# ludusProtoShieldWireless.net
KiCad netlist of a schematic drawn in EAGLE
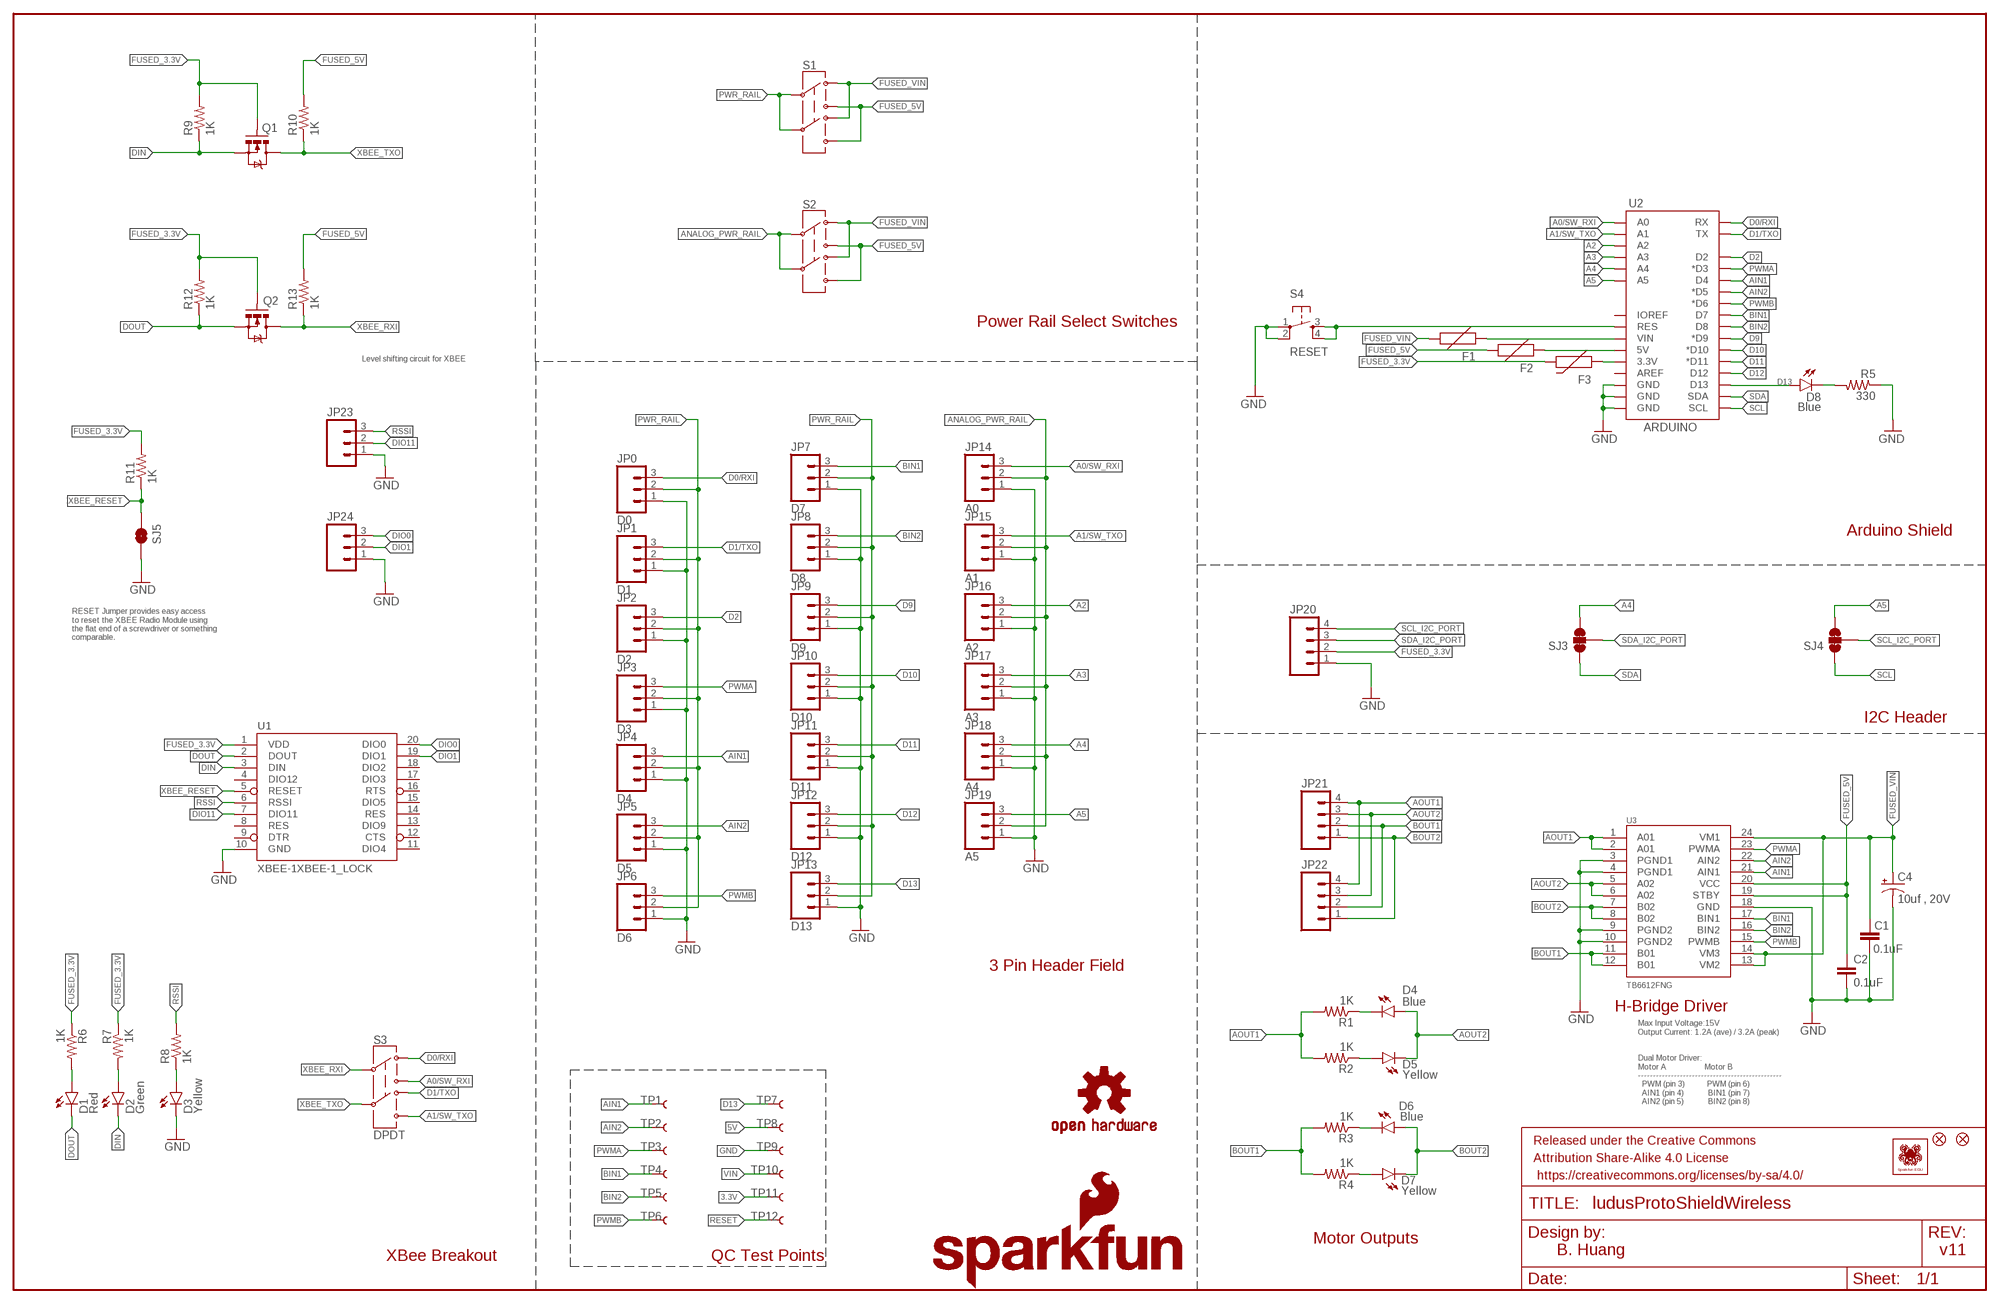
[diagram p0: schematic, sheet 1]

(export (version "E")
  (design (tool "Eeschema 10.0.6"))
  (components
    (comp (ref "C1")
      (value "0.1uF")
      (footprint "eagle-import:0603-CAP")
      (libsource (lib "eagle-import") (part "0.1UF-25V-5%(0603)"))
    )
    (comp (ref "C2")
      (value "0.1uF")
      (footprint "eagle-import:0603-CAP")
      (libsource (lib "eagle-import") (part "0.1UF-25V-5%(0603)"))
    )
    (comp (ref "C4")
      (value "10uf , 20V")
      (footprint "eagle-import:EIA3528")
      (libsource (lib "eagle-import") (part "10UF-20V-10%(TANT)"))
    )
    (comp (ref "D1")
      (value "Red")
      (footprint "eagle-import:LED-0603")
      (libsource (lib "eagle-import") (part "LED-RED0603"))
    )
    (comp (ref "D2")
      (value "Green")
      (footprint "eagle-import:LED-0603")
      (libsource (lib "eagle-import") (part "LED-GREEN0603"))
    )
    (comp (ref "D3")
      (value "Yellow")
      (footprint "eagle-import:LED-0603")
      (libsource (lib "eagle-import") (part "LED-YELLOW0603"))
    )
    (comp (ref "D4")
      (value "Blue")
      (footprint "eagle-import:LED-0603")
      (libsource (lib "eagle-import") (part "LED-BLUE0603"))
    )
    (comp (ref "D5")
      (value "Yellow")
      (footprint "eagle-import:LED-0603")
      (libsource (lib "eagle-import") (part "LED-YELLOW0603"))
    )
    (comp (ref "D6")
      (value "Blue")
      (footprint "eagle-import:LED-0603")
      (libsource (lib "eagle-import") (part "LED-BLUE0603"))
    )
    (comp (ref "D7")
      (value "Yellow")
      (footprint "eagle-import:LED-0603")
      (libsource (lib "eagle-import") (part "LED-YELLOW0603"))
    )
    (comp (ref "D8")
      (value "Blue")
      (footprint "eagle-import:LED-0603")
      (libsource (lib "eagle-import") (part "LED-BLUE0603"))
    )
    (comp (ref "F1")
      (value "PTCSMD")
      (footprint "eagle-import:PTC-1206")
      (libsource (lib "eagle-import") (part "PTCSMD"))
    )
    (comp (ref "F2")
      (value "PTCSMD")
      (footprint "eagle-import:PTC-1206")
      (libsource (lib "eagle-import") (part "PTCSMD"))
    )
    (comp (ref "F3")
      (value "PTCSMD")
      (footprint "eagle-import:PTC-1206")
      (libsource (lib "eagle-import") (part "PTCSMD"))
    )
    (comp (ref "FID1")
      (value "FIDUCIAL1X2")
      (footprint "eagle-import:FIDUCIAL-1X2")
      (libsource (lib "eagle-import") (part "FIDUCIAL1X2"))
    )
    (comp (ref "FID2")
      (value "FIDUCIAL1X2")
      (footprint "eagle-import:FIDUCIAL-1X2")
      (libsource (lib "eagle-import") (part "FIDUCIAL1X2"))
    )
    (comp (ref "FRAME1")
      (value "FRAME-LEDGER")
      (footprint "eagle-import:CREATIVE_COMMONS")
      (libsource (lib "eagle-import") (part "FRAME-LEDGER"))
    )
    (comp (ref "JP0")
      (value "D0")
      (footprint "eagle-import:1X03_LOCK")
      (libsource (lib "eagle-import") (part "M03LOCK"))
    )
    (comp (ref "JP1")
      (value "D1")
      (footprint "eagle-import:1X03_LOCK")
      (libsource (lib "eagle-import") (part "M03LOCK"))
    )
    (comp (ref "JP2")
      (value "D2")
      (footprint "eagle-import:1X03_LOCK")
      (libsource (lib "eagle-import") (part "M03LOCK"))
    )
    (comp (ref "JP3")
      (value "D3")
      (footprint "eagle-import:1X03_LOCK")
      (libsource (lib "eagle-import") (part "M03LOCK"))
    )
    (comp (ref "JP4")
      (value "D4")
      (footprint "eagle-import:1X03_LOCK")
      (libsource (lib "eagle-import") (part "M03LOCK"))
    )
    (comp (ref "JP5")
      (value "D5")
      (footprint "eagle-import:1X03_LOCK")
      (libsource (lib "eagle-import") (part "M03LOCK"))
    )
    (comp (ref "JP6")
      (value "D6")
      (footprint "eagle-import:1X03_LOCK")
      (libsource (lib "eagle-import") (part "M03LOCK"))
    )
    (comp (ref "JP7")
      (value "D7")
      (footprint "eagle-import:1X03_LOCK")
      (libsource (lib "eagle-import") (part "M03LOCK"))
    )
    (comp (ref "JP8")
      (value "D8")
      (footprint "eagle-import:1X03_LOCK")
      (libsource (lib "eagle-import") (part "M03LOCK"))
    )
    (comp (ref "JP9")
      (value "D9")
      (footprint "eagle-import:1X03_LOCK")
      (libsource (lib "eagle-import") (part "M03LOCK"))
    )
    (comp (ref "JP10")
      (value "D10")
      (footprint "eagle-import:1X03_LOCK")
      (libsource (lib "eagle-import") (part "M03LOCK"))
    )
    (comp (ref "JP11")
      (value "D11")
      (footprint "eagle-import:1X03_LOCK")
      (libsource (lib "eagle-import") (part "M03LOCK"))
    )
    (comp (ref "JP12")
      (value "D12")
      (footprint "eagle-import:1X03_LOCK")
      (libsource (lib "eagle-import") (part "M03LOCK"))
    )
    (comp (ref "JP13")
      (value "D13")
      (footprint "eagle-import:1X03_LOCK")
      (libsource (lib "eagle-import") (part "M03LOCK"))
    )
    (comp (ref "JP14")
      (value "A0")
      (footprint "eagle-import:1X03_LOCK")
      (libsource (lib "eagle-import") (part "M03LOCK"))
    )
    (comp (ref "JP15")
      (value "A1")
      (footprint "eagle-import:1X03_LOCK")
      (libsource (lib "eagle-import") (part "M03LOCK"))
    )
    (comp (ref "JP16")
      (value "A2")
      (footprint "eagle-import:1X03_LOCK")
      (libsource (lib "eagle-import") (part "M03LOCK"))
    )
    (comp (ref "JP17")
      (value "A3")
      (footprint "eagle-import:1X03_LOCK")
      (libsource (lib "eagle-import") (part "M03LOCK"))
    )
    (comp (ref "JP18")
      (value "A4")
      (footprint "eagle-import:1X03_LOCK")
      (libsource (lib "eagle-import") (part "M03LOCK"))
    )
    (comp (ref "JP19")
      (value "A5")
      (footprint "eagle-import:1X03_LOCK")
      (libsource (lib "eagle-import") (part "M03LOCK"))
    )
    (comp (ref "JP20")
      (value "M04PTH")
      (footprint "eagle-import:1X04")
      (libsource (lib "eagle-import") (part "M04PTH"))
    )
    (comp (ref "JP21")
      (value "M04PTH")
      (footprint "eagle-import:1X04")
      (libsource (lib "eagle-import") (part "M04PTH"))
    )
    (comp (ref "JP22")
      (value "M04LOCK")
      (footprint "eagle-import:1X04_LOCK")
      (libsource (lib "eagle-import") (part "M04LOCK"))
    )
    (comp (ref "JP23")
      (value "M031X03_NO_SILK")
      (footprint "eagle-import:1X03_NO_SILK")
      (libsource (lib "eagle-import") (part "M031X03_NO_SILK"))
    )
    (comp (ref "JP24")
      (value "M031X03_NO_SILK")
      (footprint "eagle-import:1X03_NO_SILK")
      (libsource (lib "eagle-import") (part "M031X03_NO_SILK"))
    )
    (comp (ref "LOGO1")
      (value "OSHW-LOGOM")
      (footprint "eagle-import:OSHW-LOGO-M")
      (libsource (lib "eagle-import") (part "OSHW-LOGOM"))
    )
    (comp (ref "LOGO2")
      (value "SFE_LOGO_NAME_FLAME.1_INCH")
      (footprint "eagle-import:SFE_LOGO_NAME_FLAME_.1")
      (libsource (lib "eagle-import") (part "SFE_LOGO_NAME_FLAME.1_INCH"))
    )
    (comp (ref "LOGO3")
      (value "SFE_LOGO_FLAME.2_INCH")
      (footprint "eagle-import:SFE_LOGO_FLAME_.2")
      (libsource (lib "eagle-import") (part "SFE_LOGO_FLAME.2_INCH"))
    )
    (comp (ref "LOGO4")
      (value "SFE_LOGO_NAME_FLAME.1_INCH")
      (footprint "eagle-import:SFE_LOGO_NAME_FLAME_.1")
      (libsource (lib "eagle-import") (part "SFE_LOGO_NAME_FLAME.1_INCH"))
    )
    (comp (ref "LOGO5")
      (value "SFE_LOGO_FLAME.2COP")
      (footprint "eagle-import:SFE_LOGO_FLAME_COPPER_.2")
      (libsource (lib "eagle-import") (part "SFE_LOGO_FLAME.2COP"))
    )
    (comp (ref "Q1")
      (value "MOSFET-NCHANNELBSS138")
      (footprint "eagle-import:SOT23-3")
      (libsource (lib "eagle-import") (part "MOSFET-NCHANNELBSS138"))
    )
    (comp (ref "Q2")
      (value "MOSFET-NCHANNELBSS138")
      (footprint "eagle-import:SOT23-3")
      (libsource (lib "eagle-import") (part "MOSFET-NCHANNELBSS138"))
    )
    (comp (ref "R1")
      (value "1K")
      (footprint "eagle-import:0603-RES")
      (libsource (lib "eagle-import") (part "1KOHM-1/10W-1%(0603)"))
    )
    (comp (ref "R2")
      (value "1K")
      (footprint "eagle-import:0603-RES")
      (libsource (lib "eagle-import") (part "1KOHM-1/10W-1%(0603)"))
    )
    (comp (ref "R3")
      (value "1K")
      (footprint "eagle-import:0603-RES")
      (libsource (lib "eagle-import") (part "1KOHM-1/10W-1%(0603)"))
    )
    (comp (ref "R4")
      (value "1K")
      (footprint "eagle-import:0603-RES")
      (libsource (lib "eagle-import") (part "1KOHM-1/10W-1%(0603)"))
    )
    (comp (ref "R5")
      (value "330")
      (footprint "eagle-import:0603-RES")
      (libsource (lib "eagle-import") (part "330OHM1/10W1%(0603)"))
    )
    (comp (ref "R6")
      (value "1K")
      (footprint "eagle-import:0603-RES")
      (libsource (lib "eagle-import") (part "1KOHM-1/10W-1%(0603)"))
    )
    (comp (ref "R7")
      (value "1K")
      (footprint "eagle-import:0603-RES")
      (libsource (lib "eagle-import") (part "1KOHM-1/10W-1%(0603)"))
    )
    (comp (ref "R8")
      (value "1K")
      (footprint "eagle-import:0603-RES")
      (libsource (lib "eagle-import") (part "1KOHM-1/10W-1%(0603)"))
    )
    (comp (ref "R9")
      (value "1K")
      (footprint "eagle-import:0603-RES")
      (libsource (lib "eagle-import") (part "1KOHM-1/10W-1%(0603)"))
    )
    (comp (ref "R10")
      (value "1K")
      (footprint "eagle-import:0603-RES")
      (libsource (lib "eagle-import") (part "1KOHM-1/10W-1%(0603)"))
    )
    (comp (ref "R11")
      (value "1K")
      (footprint "eagle-import:0603-RES")
      (libsource (lib "eagle-import") (part "1KOHM-1/10W-1%(0603)"))
    )
    (comp (ref "R12")
      (value "1K")
      (footprint "eagle-import:0603-RES")
      (libsource (lib "eagle-import") (part "1KOHM-1/10W-1%(0603)"))
    )
    (comp (ref "R13")
      (value "1K")
      (footprint "eagle-import:0603-RES")
      (libsource (lib "eagle-import") (part "1KOHM-1/10W-1%(0603)"))
    )
    (comp (ref "S1")
      (value "SWITCH-DPDTAYZ0202")
      (footprint "eagle-import:AYZ0202")
      (libsource (lib "eagle-import") (part "SWITCH-DPDTAYZ0202"))
    )
    (comp (ref "S2")
      (value "SWITCH-DPDTAYZ0202")
      (footprint "eagle-import:AYZ0202")
      (libsource (lib "eagle-import") (part "SWITCH-DPDTAYZ0202"))
    )
    (comp (ref "S3")
      (value "DPDT")
      (footprint "eagle-import:AYZ0202")
      (fields (field (name "PROD_ID") "SWCH-08179"))
      (libsource (lib "eagle-import") (part "SWITCH-DPDTAYZ0202"))
    )
    (comp (ref "S4")
      (value "RESET")
      (footprint "eagle-import:TACTILE-SWITCH-SMD")
      (libsource (lib "eagle-import") (part "TAC_SWITCHSMD"))
    )
    (comp (ref "SJ3")
      (value "JUMPER-PAD-3-NC_BY_TRACE")
      (footprint "eagle-import:PAD-JUMPER-3-3OF3_NC_BY_TRACE_YES_SILK_FULL_BOX")
      (libsource (lib "eagle-import") (part "JUMPER-PAD-3-NC_BY_TRACE"))
    )
    (comp (ref "SJ4")
      (value "JUMPER-PAD-3-NC_BY_TRACE")
      (footprint "eagle-import:PAD-JUMPER-3-3OF3_NC_BY_TRACE_YES_SILK_FULL_BOX")
      (libsource (lib "eagle-import") (part "JUMPER-PAD-3-NC_BY_TRACE"))
    )
    (comp (ref "SJ5")
      (value "SOLDERJUMPERNO")
      (footprint "eagle-import:SJ_2S-NO")
      (libsource (lib "eagle-import") (part "SOLDERJUMPERNO"))
    )
    (comp (ref "TP1")
      (value "TEST-POINT3X5")
      (footprint "eagle-import:PAD.03X.05")
      (libsource (lib "eagle-import") (part "TEST-POINT3X5"))
    )
    (comp (ref "TP2")
      (value "TEST-POINT3X5")
      (footprint "eagle-import:PAD.03X.05")
      (libsource (lib "eagle-import") (part "TEST-POINT3X5"))
    )
    (comp (ref "TP3")
      (value "TEST-POINT3X5")
      (footprint "eagle-import:PAD.03X.05")
      (libsource (lib "eagle-import") (part "TEST-POINT3X5"))
    )
    (comp (ref "TP4")
      (value "TEST-POINT3X5")
      (footprint "eagle-import:PAD.03X.05")
      (libsource (lib "eagle-import") (part "TEST-POINT3X5"))
    )
    (comp (ref "TP5")
      (value "TEST-POINT3X5")
      (footprint "eagle-import:PAD.03X.05")
      (libsource (lib "eagle-import") (part "TEST-POINT3X5"))
    )
    (comp (ref "TP6")
      (value "TEST-POINT3X5")
      (footprint "eagle-import:PAD.03X.05")
      (libsource (lib "eagle-import") (part "TEST-POINT3X5"))
    )
    (comp (ref "TP7")
      (value "TEST-POINT3X5")
      (footprint "eagle-import:PAD.03X.05")
      (libsource (lib "eagle-import") (part "TEST-POINT3X5"))
    )
    (comp (ref "TP8")
      (value "TEST-POINT3X5")
      (footprint "eagle-import:PAD.03X.05")
      (libsource (lib "eagle-import") (part "TEST-POINT3X5"))
    )
    (comp (ref "TP9")
      (value "TEST-POINT3X5")
      (footprint "eagle-import:PAD.03X.05")
      (libsource (lib "eagle-import") (part "TEST-POINT3X5"))
    )
    (comp (ref "TP10")
      (value "TEST-POINT3X5")
      (footprint "eagle-import:PAD.03X.05")
      (libsource (lib "eagle-import") (part "TEST-POINT3X5"))
    )
    (comp (ref "TP11")
      (value "TEST-POINT3X5")
      (footprint "eagle-import:PAD.03X.05")
      (libsource (lib "eagle-import") (part "TEST-POINT3X5"))
    )
    (comp (ref "TP12")
      (value "TEST-POINT3X5")
      (footprint "eagle-import:PAD.03X.05")
      (libsource (lib "eagle-import") (part "TEST-POINT3X5"))
    )
    (comp (ref "U$1")
      (value "SFE_LUDUSSFE_LUDUS-M")
      (footprint "eagle-import:SFE_LUDUS-M")
      (libsource (lib "eagle-import") (part "SFE_LUDUSSFE_LUDUS-M"))
    )
    (comp (ref "U1")
      (value "XBEE-1XBEE-1_LOCK")
      (footprint "eagle-import:XBEE-1_LOCK")
      (libsource (lib "eagle-import") (part "XBEE-1XBEE-1_LOCK"))
    )
    (comp (ref "U2")
      (value "ARDUINO")
      (footprint "eagle-import:UNO_R3_SHIELD_NOLABELS_LOCK")
      (libsource (lib "eagle-import") (part "ARDUINO_R3_SHIELDUNO_R3_SHIELD_NOLABELS_LOCK"))
    )
    (comp (ref "U3")
      (value "TB6612FNG")
      (footprint "eagle-import:SSOP24")
      (libsource (lib "eagle-import") (part "TB6612FNG"))
    )
  )
  (nets
    (net (code "1") (name "3.3V") (class "Default")
      (node (ref "F3") (pin "1") (pinfunction "1_1") (pintype "bidirectional"))
      (node (ref "TP11") (pin "P$1") (pinfunction "1_P$1") (pintype "bidirectional"))
      (node (ref "U2") (pin "3.3V") (pinfunction "3.3V_3.3V") (pintype "bidirectional"))
    )
    (net (code "2") (name "5V") (class "Default")
      (node (ref "F2") (pin "1") (pinfunction "1_1") (pintype "bidirectional"))
      (node (ref "TP8") (pin "P$1") (pinfunction "1_P$1") (pintype "bidirectional"))
      (node (ref "U2") (pin "5V") (pinfunction "5V_5V") (pintype "bidirectional"))
    )
    (net (code "3") (name "A0{slash}SW_RXI") (class "Default")
      (node (ref "JP14") (pin "3") (pinfunction "3_3") (pintype "passive"))
      (node (ref "S3") (pin "3") (pinfunction "3_3") (pintype "bidirectional"))
      (node (ref "U2") (pin "A0") (pinfunction "A0_A0") (pintype "bidirectional"))
    )
    (net (code "4") (name "A1{slash}SW_TXO") (class "Default")
      (node (ref "JP15") (pin "3") (pinfunction "3_3") (pintype "passive"))
      (node (ref "S3") (pin "6") (pinfunction "6_6") (pintype "bidirectional"))
      (node (ref "U2") (pin "A1") (pinfunction "A1_A1") (pintype "bidirectional"))
    )
    (net (code "5") (name "A2") (class "Default")
      (node (ref "JP16") (pin "3") (pinfunction "3_3") (pintype "passive"))
      (node (ref "U2") (pin "A2") (pinfunction "A2_A2") (pintype "bidirectional"))
    )
    (net (code "6") (name "A3") (class "Default")
      (node (ref "JP17") (pin "3") (pinfunction "3_3") (pintype "passive"))
      (node (ref "U2") (pin "A3") (pinfunction "A3_A3") (pintype "bidirectional"))
    )
    (net (code "7") (name "A4") (class "Default")
      (node (ref "JP18") (pin "3") (pinfunction "3_3") (pintype "passive"))
      (node (ref "SJ3") (pin "3") (pinfunction "3_3") (pintype "passive"))
      (node (ref "U2") (pin "A4") (pinfunction "A4_A4") (pintype "bidirectional"))
    )
    (net (code "8") (name "A5") (class "Default")
      (node (ref "JP19") (pin "3") (pinfunction "3_3") (pintype "passive"))
      (node (ref "SJ4") (pin "3") (pinfunction "3_3") (pintype "passive"))
      (node (ref "U2") (pin "A5") (pinfunction "A5_A5") (pintype "bidirectional"))
    )
    (net (code "9") (name "AIN1") (class "Default")
      (node (ref "JP4") (pin "3") (pinfunction "3_3") (pintype "passive"))
      (node (ref "TP1") (pin "P$1") (pinfunction "1_P$1") (pintype "bidirectional"))
      (node (ref "U2") (pin "D4") (pinfunction "D4_D4") (pintype "bidirectional"))
      (node (ref "U3") (pin "21") (pinfunction "AIN1_21") (pintype "bidirectional"))
    )
    (net (code "10") (name "AIN2") (class "Default")
      (node (ref "JP5") (pin "3") (pinfunction "3_3") (pintype "passive"))
      (node (ref "TP2") (pin "P$1") (pinfunction "1_P$1") (pintype "bidirectional"))
      (node (ref "U2") (pin "D5") (pinfunction "*D5_D5") (pintype "bidirectional"))
      (node (ref "U3") (pin "22") (pinfunction "AIN2_22") (pintype "bidirectional"))
    )
    (net (code "11") (name "ANALOG_PWR_RAIL") (class "Default")
      (node (ref "JP14") (pin "2") (pinfunction "2_2") (pintype "passive"))
      (node (ref "JP15") (pin "2") (pinfunction "2_2") (pintype "passive"))
      (node (ref "JP16") (pin "2") (pinfunction "2_2") (pintype "passive"))
      (node (ref "JP17") (pin "2") (pinfunction "2_2") (pintype "passive"))
      (node (ref "JP18") (pin "2") (pinfunction "2_2") (pintype "passive"))
      (node (ref "JP19") (pin "2") (pinfunction "2_2") (pintype "passive"))
      (node (ref "S2") (pin "2") (pinfunction "2_2") (pintype "bidirectional"))
      (node (ref "S2") (pin "5") (pinfunction "5_5") (pintype "bidirectional"))
    )
    (net (code "12") (name "AOUT1") (class "Default")
      (node (ref "JP21") (pin "4") (pinfunction "4_4") (pintype "passive"))
      (node (ref "JP22") (pin "4") (pinfunction "4_4") (pintype "passive"))
      (node (ref "R1") (pin "2") (pinfunction "2_2") (pintype "passive"))
      (node (ref "R2") (pin "2") (pinfunction "2_2") (pintype "passive"))
      (node (ref "U3") (pin "1") (pinfunction "A01_1") (pintype "bidirectional"))
      (node (ref "U3") (pin "2") (pinfunction "A01_2") (pintype "bidirectional"))
    )
    (net (code "13") (name "AOUT2") (class "Default")
      (node (ref "D4") (pin "A") (pinfunction "A_A") (pintype "passive"))
      (node (ref "D5") (pin "C") (pinfunction "C_C") (pintype "passive"))
      (node (ref "JP21") (pin "3") (pinfunction "3_3") (pintype "passive"))
      (node (ref "JP22") (pin "3") (pinfunction "3_3") (pintype "passive"))
      (node (ref "U3") (pin "5") (pinfunction "A02_5") (pintype "bidirectional"))
      (node (ref "U3") (pin "6") (pinfunction "A02_6") (pintype "bidirectional"))
    )
    (net (code "14") (name "BIN1") (class "Default")
      (node (ref "JP7") (pin "3") (pinfunction "3_3") (pintype "passive"))
      (node (ref "TP4") (pin "P$1") (pinfunction "1_P$1") (pintype "bidirectional"))
      (node (ref "U2") (pin "D7") (pinfunction "D7_D7") (pintype "bidirectional"))
      (node (ref "U3") (pin "17") (pinfunction "BIN1_17") (pintype "bidirectional"))
    )
    (net (code "15") (name "BIN2") (class "Default")
      (node (ref "JP8") (pin "3") (pinfunction "3_3") (pintype "passive"))
      (node (ref "TP5") (pin "P$1") (pinfunction "1_P$1") (pintype "bidirectional"))
      (node (ref "U2") (pin "D8") (pinfunction "D8_D8") (pintype "bidirectional"))
      (node (ref "U3") (pin "16") (pinfunction "BIN2_16") (pintype "bidirectional"))
    )
    (net (code "16") (name "BOUT1") (class "Default")
      (node (ref "JP21") (pin "2") (pinfunction "2_2") (pintype "passive"))
      (node (ref "JP22") (pin "2") (pinfunction "2_2") (pintype "passive"))
      (node (ref "R3") (pin "2") (pinfunction "2_2") (pintype "passive"))
      (node (ref "R4") (pin "2") (pinfunction "2_2") (pintype "passive"))
      (node (ref "U3") (pin "11") (pinfunction "B01_11") (pintype "bidirectional"))
      (node (ref "U3") (pin "12") (pinfunction "B01_12") (pintype "bidirectional"))
    )
    (net (code "17") (name "BOUT2") (class "Default")
      (node (ref "D6") (pin "A") (pinfunction "A_A") (pintype "passive"))
      (node (ref "D7") (pin "C") (pinfunction "C_C") (pintype "passive"))
      (node (ref "JP21") (pin "1") (pinfunction "1_1") (pintype "passive"))
      (node (ref "JP22") (pin "1") (pinfunction "1_1") (pintype "passive"))
      (node (ref "U3") (pin "7") (pinfunction "B02_7") (pintype "bidirectional"))
      (node (ref "U3") (pin "8") (pinfunction "B02_8") (pintype "bidirectional"))
    )
    (net (code "18") (name "D0{slash}RXI") (class "Default")
      (node (ref "JP0") (pin "3") (pinfunction "3_3") (pintype "passive"))
      (node (ref "S3") (pin "1") (pinfunction "1_1") (pintype "bidirectional"))
      (node (ref "U2") (pin "RX") (pinfunction "RX_RX") (pintype "bidirectional"))
    )
    (net (code "19") (name "D1{slash}TXO") (class "Default")
      (node (ref "JP1") (pin "3") (pinfunction "3_3") (pintype "passive"))
      (node (ref "S3") (pin "4") (pinfunction "4_4") (pintype "bidirectional"))
      (node (ref "U2") (pin "TX") (pinfunction "TX_TX") (pintype "bidirectional"))
    )
    (net (code "20") (name "D2") (class "Default")
      (node (ref "JP2") (pin "3") (pinfunction "3_3") (pintype "passive"))
      (node (ref "U2") (pin "D2") (pinfunction "D2_D2") (pintype "bidirectional"))
    )
    (net (code "21") (name "D9") (class "Default")
      (node (ref "JP9") (pin "3") (pinfunction "3_3") (pintype "passive"))
      (node (ref "U2") (pin "D9") (pinfunction "*D9_D9") (pintype "bidirectional"))
    )
    (net (code "22") (name "D10") (class "Default")
      (node (ref "JP10") (pin "3") (pinfunction "3_3") (pintype "passive"))
      (node (ref "U2") (pin "D10") (pinfunction "*D10_D10") (pintype "bidirectional"))
    )
    (net (code "23") (name "D11") (class "Default")
      (node (ref "JP11") (pin "3") (pinfunction "3_3") (pintype "passive"))
      (node (ref "U2") (pin "D11") (pinfunction "*D11_D11") (pintype "bidirectional"))
    )
    (net (code "24") (name "D12") (class "Default")
      (node (ref "JP12") (pin "3") (pinfunction "3_3") (pintype "passive"))
      (node (ref "U2") (pin "D12") (pinfunction "D12_D12") (pintype "bidirectional"))
    )
    (net (code "25") (name "D13") (class "Default")
      (node (ref "D8") (pin "A") (pinfunction "A_A") (pintype "passive"))
      (node (ref "JP13") (pin "3") (pinfunction "3_3") (pintype "passive"))
      (node (ref "TP7") (pin "P$1") (pinfunction "1_P$1") (pintype "bidirectional"))
      (node (ref "U2") (pin "D13") (pinfunction "D13_D13") (pintype "bidirectional"))
    )
    (net (code "26") (name "DIN") (class "Default")
      (node (ref "D2") (pin "C") (pinfunction "C_C") (pintype "passive"))
      (node (ref "Q1") (pin "2") (pinfunction "S_2") (pintype "passive"))
      (node (ref "R9") (pin "1") (pinfunction "1_1") (pintype "passive"))
      (node (ref "U1") (pin "3") (pinfunction "DIN_3") (pintype "input"))
    )
    (net (code "27") (name "DIO0") (class "Default")
      (node (ref "JP24") (pin "3") (pinfunction "3_3") (pintype "passive"))
      (node (ref "U1") (pin "20") (pinfunction "DIO0_20") (pintype "bidirectional"))
    )
    (net (code "28") (name "DIO1") (class "Default")
      (node (ref "JP24") (pin "2") (pinfunction "2_2") (pintype "passive"))
      (node (ref "U1") (pin "19") (pinfunction "DIO1_19") (pintype "bidirectional"))
    )
    (net (code "29") (name "DIO11") (class "Default")
      (node (ref "JP23") (pin "2") (pinfunction "2_2") (pintype "passive"))
      (node (ref "U1") (pin "7") (pinfunction "DIO11_7") (pintype "bidirectional"))
    )
    (net (code "30") (name "DOUT") (class "Default")
      (node (ref "D1") (pin "C") (pinfunction "C_C") (pintype "passive"))
      (node (ref "Q2") (pin "2") (pinfunction "S_2") (pintype "passive"))
      (node (ref "R12") (pin "1") (pinfunction "1_1") (pintype "passive"))
      (node (ref "U1") (pin "2") (pinfunction "DOUT_2") (pintype "output"))
    )
    (net (code "31") (name "FUSED_3.3V") (class "Default")
      (node (ref "F3") (pin "2") (pinfunction "2_2") (pintype "bidirectional"))
      (node (ref "JP20") (pin "2") (pinfunction "2_2") (pintype "passive"))
      (node (ref "Q1") (pin "1") (pinfunction "G_1") (pintype "passive"))
      (node (ref "Q2") (pin "1") (pinfunction "G_1") (pintype "passive"))
      (node (ref "R11") (pin "2") (pinfunction "2_2") (pintype "passive"))
      (node (ref "R12") (pin "2") (pinfunction "2_2") (pintype "passive"))
      (node (ref "R6") (pin "1") (pinfunction "1_1") (pintype "passive"))
      (node (ref "R7") (pin "1") (pinfunction "1_1") (pintype "passive"))
      (node (ref "R9") (pin "2") (pinfunction "2_2") (pintype "passive"))
      (node (ref "U1") (pin "1") (pinfunction "VDD_1") (pintype "power_in"))
    )
    (net (code "32") (name "FUSED_5V") (class "Default")
      (node (ref "C2") (pin "1") (pinfunction "1_1") (pintype "passive"))
      (node (ref "F2") (pin "2") (pinfunction "2_2") (pintype "bidirectional"))
      (node (ref "R10") (pin "2") (pinfunction "2_2") (pintype "passive"))
      (node (ref "R13") (pin "2") (pinfunction "2_2") (pintype "passive"))
      (node (ref "S1") (pin "3") (pinfunction "3_3") (pintype "bidirectional"))
      (node (ref "S1") (pin "6") (pinfunction "6_6") (pintype "bidirectional"))
      (node (ref "S2") (pin "3") (pinfunction "3_3") (pintype "bidirectional"))
      (node (ref "S2") (pin "6") (pinfunction "6_6") (pintype "bidirectional"))
      (node (ref "U3") (pin "19") (pinfunction "STBY_19") (pintype "bidirectional"))
      (node (ref "U3") (pin "20") (pinfunction "VCC_20") (pintype "bidirectional"))
    )
    (net (code "33") (name "FUSED_VIN") (class "Default")
      (node (ref "C1") (pin "1") (pinfunction "1_1") (pintype "passive"))
      (node (ref "C4") (pin "A") (pinfunction "+_A") (pintype "passive"))
      (node (ref "F1") (pin "2") (pinfunction "2_2") (pintype "bidirectional"))
      (node (ref "S1") (pin "1") (pinfunction "1_1") (pintype "bidirectional"))
      (node (ref "S1") (pin "4") (pinfunction "4_4") (pintype "bidirectional"))
      (node (ref "S2") (pin "1") (pinfunction "1_1") (pintype "bidirectional"))
      (node (ref "S2") (pin "4") (pinfunction "4_4") (pintype "bidirectional"))
      (node (ref "U3") (pin "13") (pinfunction "VM2_13") (pintype "bidirectional"))
      (node (ref "U3") (pin "14") (pinfunction "VM3_14") (pintype "bidirectional"))
      (node (ref "U3") (pin "24") (pinfunction "VM1_24") (pintype "bidirectional"))
    )
    (net (code "34") (name "GND") (class "Default")
      (node (ref "C1") (pin "2") (pinfunction "2_2") (pintype "passive"))
      (node (ref "C2") (pin "2") (pinfunction "2_2") (pintype "passive"))
      (node (ref "C4") (pin "C") (pinfunction "-_C") (pintype "passive"))
      (node (ref "D3") (pin "C") (pinfunction "C_C") (pintype "passive"))
      (node (ref "JP0") (pin "1") (pinfunction "1_1") (pintype "passive"))
      (node (ref "JP1") (pin "1") (pinfunction "1_1") (pintype "passive"))
      (node (ref "JP10") (pin "1") (pinfunction "1_1") (pintype "passive"))
      (node (ref "JP11") (pin "1") (pinfunction "1_1") (pintype "passive"))
      (node (ref "JP12") (pin "1") (pinfunction "1_1") (pintype "passive"))
      (node (ref "JP13") (pin "1") (pinfunction "1_1") (pintype "passive"))
      (node (ref "JP14") (pin "1") (pinfunction "1_1") (pintype "passive"))
      (node (ref "JP15") (pin "1") (pinfunction "1_1") (pintype "passive"))
      (node (ref "JP16") (pin "1") (pinfunction "1_1") (pintype "passive"))
      (node (ref "JP17") (pin "1") (pinfunction "1_1") (pintype "passive"))
      (node (ref "JP18") (pin "1") (pinfunction "1_1") (pintype "passive"))
      (node (ref "JP19") (pin "1") (pinfunction "1_1") (pintype "passive"))
      (node (ref "JP2") (pin "1") (pinfunction "1_1") (pintype "passive"))
      (node (ref "JP20") (pin "1") (pinfunction "1_1") (pintype "passive"))
      (node (ref "JP23") (pin "1") (pinfunction "1_1") (pintype "passive"))
      (node (ref "JP24") (pin "1") (pinfunction "1_1") (pintype "passive"))
      (node (ref "JP3") (pin "1") (pinfunction "1_1") (pintype "passive"))
      (node (ref "JP4") (pin "1") (pinfunction "1_1") (pintype "passive"))
      (node (ref "JP5") (pin "1") (pinfunction "1_1") (pintype "passive"))
      (node (ref "JP6") (pin "1") (pinfunction "1_1") (pintype "passive"))
      (node (ref "JP7") (pin "1") (pinfunction "1_1") (pintype "passive"))
      (node (ref "JP8") (pin "1") (pinfunction "1_1") (pintype "passive"))
      (node (ref "JP9") (pin "1") (pinfunction "1_1") (pintype "passive"))
      (node (ref "R5") (pin "1") (pinfunction "1_1") (pintype "passive"))
      (node (ref "S4") (pin "1") (pinfunction "1_1") (pintype "passive"))
      (node (ref "S4") (pin "2") (pinfunction "2_2") (pintype "passive"))
      (node (ref "SJ5") (pin "2") (pinfunction "2_2") (pintype "passive"))
      (node (ref "TP9") (pin "P$1") (pinfunction "1_P$1") (pintype "bidirectional"))
      (node (ref "U1") (pin "10") (pinfunction "GND_10") (pintype "power_in"))
      (node (ref "U2") (pin "GND@0") (pinfunction "GND_GND@0") (pintype "bidirectional"))
      (node (ref "U2") (pin "GND@1") (pinfunction "GND_GND@1") (pintype "bidirectional"))
      (node (ref "U2") (pin "GND@2") (pinfunction "GND_GND@2") (pintype "bidirectional"))
      (node (ref "U3") (pin "10") (pinfunction "PGND2_10") (pintype "bidirectional"))
      (node (ref "U3") (pin "18") (pinfunction "GND_18") (pintype "bidirectional"))
      (node (ref "U3") (pin "3") (pinfunction "PGND1_3") (pintype "bidirectional"))
      (node (ref "U3") (pin "4") (pinfunction "PGND1_4") (pintype "bidirectional"))
      (node (ref "U3") (pin "9") (pinfunction "PGND2_9") (pintype "bidirectional"))
    )
    (net (code "35") (name "Net-(D1-PadA)") (class "Default")
      (node (ref "D1") (pin "A") (pinfunction "A_A") (pintype "passive"))
      (node (ref "R6") (pin "2") (pinfunction "2_2") (pintype "passive"))
    )
    (net (code "36") (name "Net-(D2-PadA)") (class "Default")
      (node (ref "D2") (pin "A") (pinfunction "A_A") (pintype "passive"))
      (node (ref "R7") (pin "2") (pinfunction "2_2") (pintype "passive"))
    )
    (net (code "37") (name "Net-(D3-PadA)") (class "Default")
      (node (ref "D3") (pin "A") (pinfunction "A_A") (pintype "passive"))
      (node (ref "R8") (pin "1") (pinfunction "1_1") (pintype "passive"))
    )
    (net (code "38") (name "Net-(D4-PadC)") (class "Default")
      (node (ref "D4") (pin "C") (pinfunction "C_C") (pintype "passive"))
      (node (ref "R1") (pin "1") (pinfunction "1_1") (pintype "passive"))
    )
    (net (code "39") (name "Net-(D5-PadA)") (class "Default")
      (node (ref "D5") (pin "A") (pinfunction "A_A") (pintype "passive"))
      (node (ref "R2") (pin "1") (pinfunction "1_1") (pintype "passive"))
    )
    (net (code "40") (name "Net-(D6-PadC)") (class "Default")
      (node (ref "D6") (pin "C") (pinfunction "C_C") (pintype "passive"))
      (node (ref "R3") (pin "1") (pinfunction "1_1") (pintype "passive"))
    )
    (net (code "41") (name "Net-(D7-PadA)") (class "Default")
      (node (ref "D7") (pin "A") (pinfunction "A_A") (pintype "passive"))
      (node (ref "R4") (pin "1") (pinfunction "1_1") (pintype "passive"))
    )
    (net (code "42") (name "Net-(D8-PadC)") (class "Default")
      (node (ref "D8") (pin "C") (pinfunction "C_C") (pintype "passive"))
      (node (ref "R5") (pin "2") (pinfunction "2_2") (pintype "passive"))
    )
    (net (code "43") (name "PWMA") (class "Default")
      (node (ref "JP3") (pin "3") (pinfunction "3_3") (pintype "passive"))
      (node (ref "TP3") (pin "P$1") (pinfunction "1_P$1") (pintype "bidirectional"))
      (node (ref "U2") (pin "D3") (pinfunction "*D3_D3") (pintype "bidirectional"))
      (node (ref "U3") (pin "23") (pinfunction "PWMA_23") (pintype "bidirectional"))
    )
    (net (code "44") (name "PWMB") (class "Default")
      (node (ref "JP6") (pin "3") (pinfunction "3_3") (pintype "passive"))
      (node (ref "TP6") (pin "P$1") (pinfunction "1_P$1") (pintype "bidirectional"))
      (node (ref "U2") (pin "D6") (pinfunction "*D6_D6") (pintype "bidirectional"))
      (node (ref "U3") (pin "15") (pinfunction "PWMB_15") (pintype "bidirectional"))
    )
    (net (code "45") (name "PWR_RAIL") (class "Default")
      (node (ref "JP0") (pin "2") (pinfunction "2_2") (pintype "passive"))
      (node (ref "JP1") (pin "2") (pinfunction "2_2") (pintype "passive"))
      (node (ref "JP10") (pin "2") (pinfunction "2_2") (pintype "passive"))
      (node (ref "JP11") (pin "2") (pinfunction "2_2") (pintype "passive"))
      (node (ref "JP12") (pin "2") (pinfunction "2_2") (pintype "passive"))
      (node (ref "JP13") (pin "2") (pinfunction "2_2") (pintype "passive"))
      (node (ref "JP2") (pin "2") (pinfunction "2_2") (pintype "passive"))
      (node (ref "JP3") (pin "2") (pinfunction "2_2") (pintype "passive"))
      (node (ref "JP4") (pin "2") (pinfunction "2_2") (pintype "passive"))
      (node (ref "JP5") (pin "2") (pinfunction "2_2") (pintype "passive"))
      (node (ref "JP6") (pin "2") (pinfunction "2_2") (pintype "passive"))
      (node (ref "JP7") (pin "2") (pinfunction "2_2") (pintype "passive"))
      (node (ref "JP8") (pin "2") (pinfunction "2_2") (pintype "passive"))
      (node (ref "JP9") (pin "2") (pinfunction "2_2") (pintype "passive"))
      (node (ref "S1") (pin "2") (pinfunction "2_2") (pintype "bidirectional"))
      (node (ref "S1") (pin "5") (pinfunction "5_5") (pintype "bidirectional"))
    )
    (net (code "46") (name "RESET") (class "Default")
      (node (ref "S4") (pin "3") (pinfunction "3_3") (pintype "passive"))
      (node (ref "S4") (pin "4") (pinfunction "4_4") (pintype "passive"))
      (node (ref "TP12") (pin "P$1") (pinfunction "1_P$1") (pintype "bidirectional"))
      (node (ref "U2") (pin "RES") (pinfunction "RES_RES") (pintype "bidirectional"))
    )
    (net (code "47") (name "RSSI") (class "Default")
      (node (ref "JP23") (pin "3") (pinfunction "3_3") (pintype "passive"))
      (node (ref "R8") (pin "2") (pinfunction "2_2") (pintype "passive"))
      (node (ref "U1") (pin "6") (pinfunction "RSSI_6") (pintype "bidirectional"))
    )
    (net (code "48") (name "SCL") (class "Default")
      (node (ref "SJ4") (pin "1") (pinfunction "1_1") (pintype "passive"))
      (node (ref "U2") (pin "SCL") (pinfunction "SCL_SCL") (pintype "bidirectional"))
    )
    (net (code "49") (name "SCL_I2C_PORT") (class "Default")
      (node (ref "JP20") (pin "4") (pinfunction "4_4") (pintype "passive"))
      (node (ref "SJ4") (pin "2") (pinfunction "2_2") (pintype "passive"))
    )
    (net (code "50") (name "SDA") (class "Default")
      (node (ref "SJ3") (pin "1") (pinfunction "1_1") (pintype "passive"))
      (node (ref "U2") (pin "SDA") (pinfunction "SDA_SDA") (pintype "bidirectional"))
    )
    (net (code "51") (name "SDA_I2C_PORT") (class "Default")
      (node (ref "JP20") (pin "3") (pinfunction "3_3") (pintype "passive"))
      (node (ref "SJ3") (pin "2") (pinfunction "2_2") (pintype "passive"))
    )
    (net (code "52") (name "VIN") (class "Default")
      (node (ref "F1") (pin "1") (pinfunction "1_1") (pintype "bidirectional"))
      (node (ref "TP10") (pin "P$1") (pinfunction "1_P$1") (pintype "bidirectional"))
      (node (ref "U2") (pin "VIN") (pinfunction "VIN_VIN") (pintype "bidirectional"))
    )
    (net (code "53") (name "XBEE_RESET") (class "Default")
      (node (ref "R11") (pin "1") (pinfunction "1_1") (pintype "passive"))
      (node (ref "SJ5") (pin "1") (pinfunction "1_1") (pintype "passive"))
      (node (ref "U1") (pin "5") (pinfunction "RESET_5") (pintype "input"))
    )
    (net (code "54") (name "XBEE_RXI") (class "Default")
      (node (ref "Q2") (pin "3") (pinfunction "D_3") (pintype "passive"))
      (node (ref "R13") (pin "1") (pinfunction "1_1") (pintype "passive"))
      (node (ref "S3") (pin "2") (pinfunction "2_2") (pintype "bidirectional"))
    )
    (net (code "55") (name "XBEE_TXO") (class "Default")
      (node (ref "Q1") (pin "3") (pinfunction "D_3") (pintype "passive"))
      (node (ref "R10") (pin "1") (pinfunction "1_1") (pintype "passive"))
      (node (ref "S3") (pin "5") (pinfunction "5_5") (pintype "bidirectional"))
    )
    (net (code "56") (name "unconnected-(U1-CTS-Pad12)") (class "Default")
      (node (ref "U1") (pin "12") (pinfunction "CTS_12") (pintype "output"))
    )
    (net (code "57") (name "unconnected-(U1-DIO2-Pad18)") (class "Default")
      (node (ref "U1") (pin "18") (pinfunction "DIO2_18") (pintype "bidirectional"))
    )
    (net (code "58") (name "unconnected-(U1-DIO3-Pad17)") (class "Default")
      (node (ref "U1") (pin "17") (pinfunction "DIO3_17") (pintype "bidirectional"))
    )
    (net (code "59") (name "unconnected-(U1-DIO4-Pad11)") (class "Default")
      (node (ref "U1") (pin "11") (pinfunction "DIO4_11") (pintype "bidirectional"))
    )
    (net (code "60") (name "unconnected-(U1-DIO5-Pad15)") (class "Default")
      (node (ref "U1") (pin "15") (pinfunction "DIO5_15") (pintype "bidirectional"))
    )
    (net (code "61") (name "unconnected-(U1-DIO9-Pad13)") (class "Default")
      (node (ref "U1") (pin "13") (pinfunction "DIO9_13") (pintype "bidirectional"))
    )
    (net (code "62") (name "unconnected-(U1-DIO12-Pad4)") (class "Default")
      (node (ref "U1") (pin "4") (pinfunction "DIO12_4") (pintype "bidirectional"))
    )
    (net (code "63") (name "unconnected-(U1-DTR-Pad9)") (class "Default")
      (node (ref "U1") (pin "9") (pinfunction "DTR_9") (pintype "bidirectional"))
    )
    (net (code "64") (name "unconnected-(U1-RES-Pad8)") (class "Default")
      (node (ref "U1") (pin "8") (pinfunction "RES_8") (pintype "bidirectional"))
    )
    (net (code "65") (name "unconnected-(U1-RES-Pad14)") (class "Default")
      (node (ref "U1") (pin "14") (pinfunction "RES_14") (pintype "bidirectional"))
    )
    (net (code "66") (name "unconnected-(U1-RTS-Pad16)") (class "Default")
      (node (ref "U1") (pin "16") (pinfunction "RTS_16") (pintype "input"))
    )
    (net (code "67") (name "unconnected-(U2-PadAREF)") (class "Default")
      (node (ref "U2") (pin "AREF") (pinfunction "AREF_AREF") (pintype "bidirectional"))
    )
    (net (code "68") (name "unconnected-(U2-PadIOREF)") (class "Default")
      (node (ref "U2") (pin "IOREF") (pinfunction "IOREF_IOREF") (pintype "bidirectional"))
    )
  )
)
